# nixie_test_v2.net
KiCad netlist of a schematic drawn in EAGLE
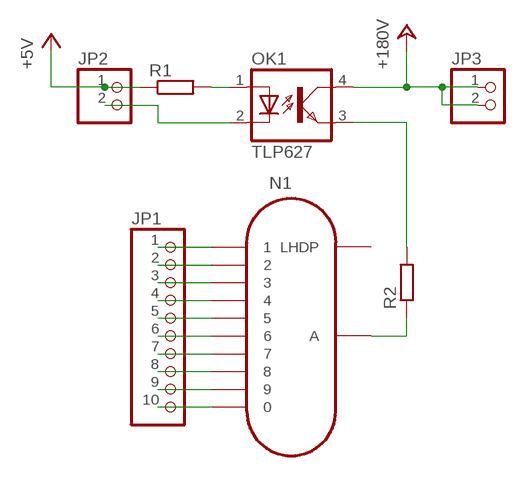
[diagram p0: schematic, sheet 1]

(export (version "E")
  (design (tool "Eeschema 10.0.6"))
  (components
    (comp (ref "JP1")
      (value "PINHD-1X10")
      (footprint "eagle-import:1X10")
      (libsource (lib "eagle-import") (part "PINHD-1X10"))
    )
    (comp (ref "JP2")
      (value "PINHD-1X2")
      (footprint "eagle-import:1X02")
      (libsource (lib "eagle-import") (part "PINHD-1X2"))
    )
    (comp (ref "JP3")
      (value "PINHD-1X2")
      (footprint "eagle-import:1X02")
      (libsource (lib "eagle-import") (part "PINHD-1X2"))
    )
    (comp (ref "N1")
      (value "IN-12B")
      (footprint "eagle-import:IN-12")
      (libsource (lib "eagle-import") (part "IN-12B"))
    )
    (comp (ref "OK1")
      (value "TLP627")
      (footprint "eagle-import:4-SMD")
      (libsource (lib "eagle-import") (part "TLP627"))
    )
    (comp (ref "R1")
      (value "R-EU_R0805")
      (footprint "eagle-import:R0805")
      (libsource (lib "eagle-import") (part "R-EU_R0805"))
    )
    (comp (ref "R2")
      (value "R-EU_10")
      (footprint "eagle-import:0207_10")
      (libsource (lib "eagle-import") (part "R-EU_10"))
    )
  )
  (nets
    (net (code "1") (name "+5V") (class "Default")
      (node (ref "JP2") (pin "1") (pinfunction "1_1") (pintype "passive"))
      (node (ref "R1") (pin "1") (pinfunction "1_1") (pintype "passive"))
    )
    (net (code "2") (name "+180V") (class "Default")
      (node (ref "JP3") (pin "1") (pinfunction "1_1") (pintype "passive"))
      (node (ref "JP3") (pin "2") (pinfunction "2_2") (pintype "passive"))
      (node (ref "OK1") (pin "4") (pinfunction "COL_4") (pintype "passive"))
    )
    (net (code "3") (name "Net-(JP1-Pad1)") (class "Default")
      (node (ref "JP1") (pin "1") (pinfunction "1_1") (pintype "passive"))
      (node (ref "N1") (pin "1") (pinfunction "1_1") (pintype "bidirectional"))
    )
    (net (code "4") (name "Net-(JP1-Pad2)") (class "Default")
      (node (ref "JP1") (pin "2") (pinfunction "2_2") (pintype "passive"))
      (node (ref "N1") (pin "2") (pinfunction "2_2") (pintype "bidirectional"))
    )
    (net (code "5") (name "Net-(JP1-Pad3)") (class "Default")
      (node (ref "JP1") (pin "3") (pinfunction "3_3") (pintype "passive"))
      (node (ref "N1") (pin "3") (pinfunction "3_3") (pintype "bidirectional"))
    )
    (net (code "6") (name "Net-(JP1-Pad4)") (class "Default")
      (node (ref "JP1") (pin "4") (pinfunction "4_4") (pintype "passive"))
      (node (ref "N1") (pin "4") (pinfunction "4_4") (pintype "bidirectional"))
    )
    (net (code "7") (name "Net-(JP1-Pad5)") (class "Default")
      (node (ref "JP1") (pin "5") (pinfunction "5_5") (pintype "passive"))
      (node (ref "N1") (pin "5") (pinfunction "5_5") (pintype "bidirectional"))
    )
    (net (code "8") (name "Net-(JP1-Pad6)") (class "Default")
      (node (ref "JP1") (pin "6") (pinfunction "6_6") (pintype "passive"))
      (node (ref "N1") (pin "6") (pinfunction "6_6") (pintype "bidirectional"))
    )
    (net (code "9") (name "Net-(JP1-Pad7)") (class "Default")
      (node (ref "JP1") (pin "7") (pinfunction "7_7") (pintype "passive"))
      (node (ref "N1") (pin "7") (pinfunction "7_7") (pintype "bidirectional"))
    )
    (net (code "10") (name "Net-(JP1-Pad8)") (class "Default")
      (node (ref "JP1") (pin "8") (pinfunction "8_8") (pintype "passive"))
      (node (ref "N1") (pin "8") (pinfunction "8_8") (pintype "bidirectional"))
    )
    (net (code "11") (name "Net-(JP1-Pad9)") (class "Default")
      (node (ref "JP1") (pin "9") (pinfunction "9_9") (pintype "passive"))
      (node (ref "N1") (pin "9") (pinfunction "9_9") (pintype "bidirectional"))
    )
    (net (code "12") (name "Net-(JP1-Pad10)") (class "Default")
      (node (ref "JP1") (pin "10") (pinfunction "10_10") (pintype "passive"))
      (node (ref "N1") (pin "0") (pinfunction "0_0") (pintype "bidirectional"))
    )
    (net (code "13") (name "Net-(N1-PadA)") (class "Default")
      (node (ref "N1") (pin "A") (pinfunction "A_A") (pintype "bidirectional"))
      (node (ref "R2") (pin "1") (pinfunction "1_1") (pintype "passive"))
    )
    (net (code "14") (name "Net-(OK1-A)") (class "Default")
      (node (ref "OK1") (pin "1") (pinfunction "A_1") (pintype "passive"))
      (node (ref "R1") (pin "2") (pinfunction "2_2") (pintype "passive"))
    )
    (net (code "15") (name "Net-(OK1-C)") (class "Default")
      (node (ref "JP2") (pin "2") (pinfunction "2_2") (pintype "passive"))
      (node (ref "OK1") (pin "2") (pinfunction "C_2") (pintype "passive"))
    )
    (net (code "16") (name "Net-(OK1-EMIT)") (class "Default")
      (node (ref "OK1") (pin "3") (pinfunction "EMIT_3") (pintype "passive"))
      (node (ref "R2") (pin "2") (pinfunction "2_2") (pintype "passive"))
    )
    (net (code "17") (name "unconnected-(N1-PadLHDP)") (class "Default")
      (node (ref "N1") (pin "LHDP") (pinfunction "LHDP_LHDP") (pintype "bidirectional"))
    )
  )
)
